# Puzzle_Tachometer-v1_1.net
KiCad netlist of a schematic drawn in EAGLE
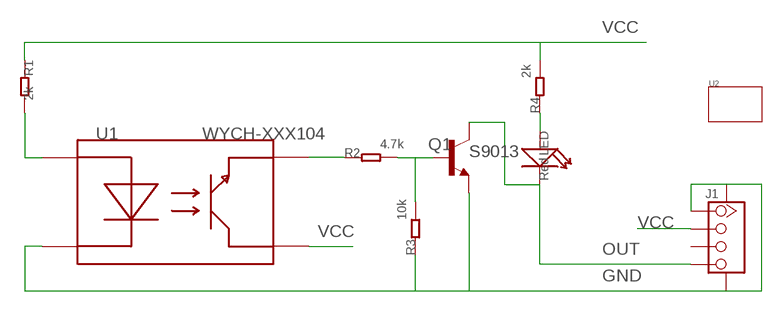
[diagram p0: schematic, sheet 1]

(export (version "E")
  (design (tool "Eeschema 10.0.6"))
  (components
    (comp (ref "J1")
      (value "TWIG-4P-2.0-SMD-FEMALE-REINFORCE'DD'")
      (footprint "eagle-import:4P-SMD-2.0")
      (libsource (lib "eagle-import") (part "TWIG-4P-2.0-SMD-FEMALE-REINFORCE'DD'"))
    )
    (comp (ref "LED")
      (value "Red")
      (footprint "eagle-import:LED-0603")
      (libsource (lib "eagle-import") (part "LED'0603'"))
    )
    (comp (ref "Q1")
      (value "S9013")
      (footprint "eagle-import:SOT23-3")
      (libsource (lib "eagle-import") (part "TRANSISTOR_NPNSOT23-3"))
    )
    (comp (ref "R1")
      (value "2k")
      (footprint "eagle-import:R0603")
      (libsource (lib "eagle-import") (part "R-0603"))
    )
    (comp (ref "R2")
      (value "4.7k")
      (footprint "eagle-import:R0603")
      (libsource (lib "eagle-import") (part "R-0603"))
    )
    (comp (ref "R3")
      (value "10k")
      (footprint "eagle-import:R0603")
      (libsource (lib "eagle-import") (part "R-0603"))
    )
    (comp (ref "R4")
      (value "2k")
      (footprint "eagle-import:R0603")
      (libsource (lib "eagle-import") (part "R-0603"))
    )
    (comp (ref "U1")
      (value "WYCH-XXX104")
      (footprint "eagle-import:WYCH104")
      (libsource (lib "eagle-import") (part "WYCH-XXX104"))
    )
    (comp (ref "U2")
      (value "TWIG-2U")
      (footprint "eagle-import:2U-DIM-W_-DRILL")
      (libsource (lib "eagle-import") (part "TWIG-2U"))
    )
  )
  (nets
    (net (code "1") (name "/GND") (class "Default")
      (node (ref "J1") (pin "1") (pinfunction "1_1") (pintype "bidirectional"))
      (node (ref "J1") (pin "SS1") (pinfunction "SS1_SS1") (pintype "bidirectional"))
      (node (ref "J1") (pin "SS2") (pinfunction "SS2_SS2") (pintype "bidirectional"))
      (node (ref "Q1") (pin "2") (pinfunction "E_2") (pintype "passive"))
      (node (ref "R3") (pin "1") (pinfunction "1_1") (pintype "passive"))
      (node (ref "U1") (pin "2") (pinfunction "2_2") (pintype "bidirectional"))
    )
    (net (code "2") (name "/OUT") (class "Default")
      (node (ref "J1") (pin "4") (pinfunction "4_4") (pintype "bidirectional"))
      (node (ref "LED") (pin "-") (pinfunction "-_-") (pintype "passive"))
      (node (ref "Q1") (pin "3") (pinfunction "C_3") (pintype "passive"))
    )
    (net (code "3") (name "/VCC") (class "Default")
      (node (ref "J1") (pin "2") (pinfunction "2_2") (pintype "bidirectional"))
      (node (ref "R1") (pin "1") (pinfunction "1_1") (pintype "passive"))
      (node (ref "R4") (pin "2") (pinfunction "2_2") (pintype "passive"))
      (node (ref "U1") (pin "3") (pinfunction "3_3") (pintype "bidirectional"))
    )
    (net (code "4") (name "Net-(LED-Pad+)") (class "Default")
      (node (ref "LED") (pin "+") (pinfunction "+_+") (pintype "passive"))
      (node (ref "R4") (pin "1") (pinfunction "1_1") (pintype "passive"))
    )
    (net (code "5") (name "Net-(Q1-B)") (class "Default")
      (node (ref "Q1") (pin "1") (pinfunction "B_1") (pintype "passive"))
      (node (ref "R2") (pin "2") (pinfunction "2_2") (pintype "passive"))
      (node (ref "R3") (pin "2") (pinfunction "2_2") (pintype "passive"))
    )
    (net (code "6") (name "Net-(R1-Pad2)") (class "Default")
      (node (ref "R1") (pin "2") (pinfunction "2_2") (pintype "passive"))
      (node (ref "U1") (pin "1") (pinfunction "1_1") (pintype "bidirectional"))
    )
    (net (code "7") (name "Net-(R2-Pad1)") (class "Default")
      (node (ref "R2") (pin "1") (pinfunction "1_1") (pintype "passive"))
      (node (ref "U1") (pin "4") (pinfunction "4_4") (pintype "bidirectional"))
    )
    (net (code "8") (name "unconnected-(J1-Pad3)") (class "Default")
      (node (ref "J1") (pin "3") (pinfunction "3_3") (pintype "bidirectional"))
    )
  )
)
